# Xe_VDK_Schematic.net
KiCad netlist of a schematic drawn in Altium Designer
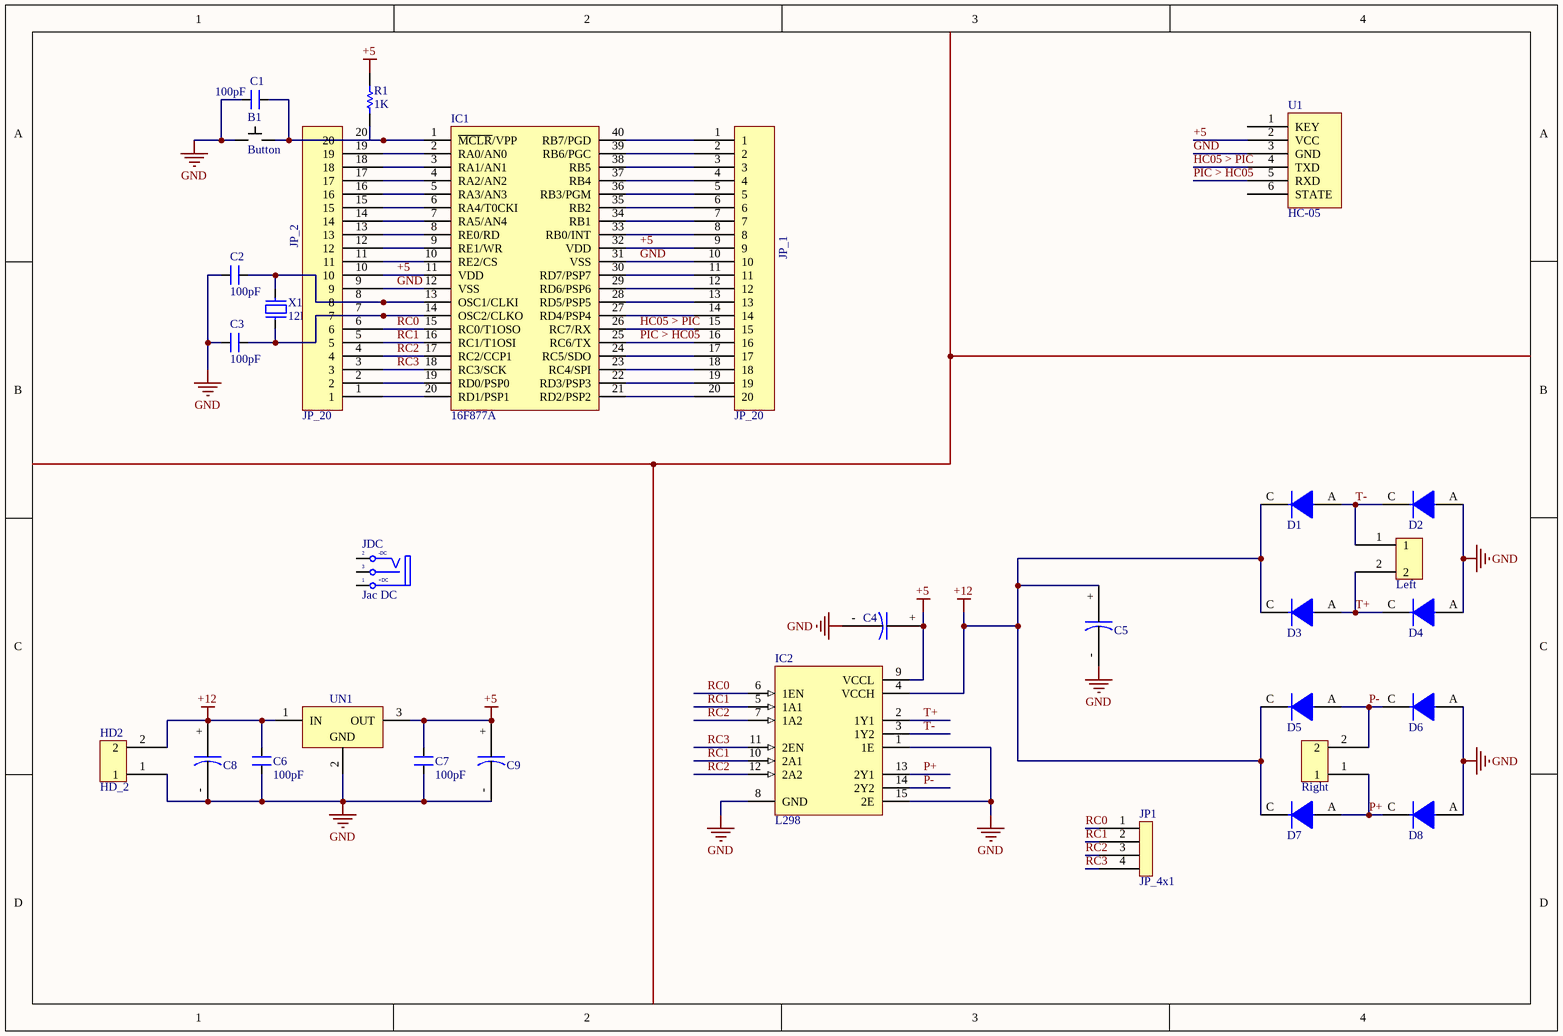
[diagram p0: Xe_VDK_Schematic.SchDoc]

(export (version "E")
  (design (tool "Eeschema 10.0.6"))
  (components
    (comp (ref "B1")
      (value "Button")
      (footprint "Button - 4-pin")
      (libsource (lib "LuongTanDat") (part "Button"))
    )
    (comp (ref "C1")
      (value "100pF")
      (footprint "CN1")
      (description "Cap np  1pF - 472pF")
      (libsource (lib "syhaunguyen") (part "CN1"))
    )
    (comp (ref "C2")
      (value "100pF")
      (footprint "CN1")
      (description "Cap np  1pF - 472pF")
      (libsource (lib "syhaunguyen") (part "CN1"))
    )
    (comp (ref "C3")
      (value "100pF")
      (footprint "CN1")
      (description "Cap np  1pF - 472pF")
      (libsource (lib "syhaunguyen") (part "CN1"))
    )
    (comp (ref "C4")
      (value "Pol-Cap")
      (footprint "Pol_200mil")
      (description "Tụ điện phân cực")
      (libsource (lib "LuongTanDat") (part "Pol-Cap"))
    )
    (comp (ref "C5")
      (value "Pol-Cap")
      (footprint "Pol_200mil")
      (description "Tụ điện phân cực")
      (libsource (lib "LuongTanDat") (part "Pol-Cap"))
    )
    (comp (ref "C6")
      (value "100pF")
      (footprint "CN1")
      (description "Cap np  1pF - 472pF")
      (libsource (lib "syhaunguyen") (part "CN1"))
    )
    (comp (ref "C7")
      (value "100pF")
      (footprint "CN1")
      (description "Cap np  1pF - 472pF")
      (libsource (lib "syhaunguyen") (part "CN1"))
    )
    (comp (ref "C8")
      (value "Pol-Cap")
      (footprint "POL_250mil")
      (description "Tụ điện phân cực")
      (libsource (lib "LuongTanDat") (part "Pol-Cap"))
    )
    (comp (ref "C9")
      (value "Pol-Cap")
      (footprint "POL_250mil")
      (description "Tụ điện phân cực")
      (libsource (lib "LuongTanDat") (part "Pol-Cap"))
    )
    (comp (ref "D1") (value "Diode") (footprint "Diode") (libsource (lib "LuongTanDat") (part "Diode")))
    (comp (ref "D2") (value "Diode") (footprint "Diode") (libsource (lib "LuongTanDat") (part "Diode")))
    (comp (ref "D3") (value "Diode") (footprint "Diode") (libsource (lib "LuongTanDat") (part "Diode")))
    (comp (ref "D4") (value "Diode") (footprint "Diode") (libsource (lib "LuongTanDat") (part "Diode")))
    (comp (ref "D5") (value "Diode") (footprint "Diode") (libsource (lib "LuongTanDat") (part "Diode")))
    (comp (ref "D6") (value "Diode") (footprint "Diode") (libsource (lib "LuongTanDat") (part "Diode")))
    (comp (ref "D7") (value "Diode") (footprint "Diode") (libsource (lib "LuongTanDat") (part "Diode")))
    (comp (ref "D8") (value "Diode") (footprint "Diode") (libsource (lib "LuongTanDat") (part "Diode")))
    (comp (ref "HD2") (value "HD_2") (footprint "Header 2") (libsource (lib "LuongTanDat") (part "HD_2")))
    (comp (ref "IC1")
      (value "16F877A")
      (footprint "DIP40/W0.6")
      (description "8K FLASH, 368B RAM, 256B EFROM")
      (fields (field (name "COPYRIGHT BY") "VanDungEvn"))
      (libsource (lib "syhaunguyen") (part "16F877"))
    )
    (comp (ref "IC2")
      (value "L298")
      (footprint "DIP15SL2")
      (description "Dual Full-H Driver")
      (fields (field (name "PUBLISHER") "Altium Limited"))
      (libsource (lib "VioletofSun") (part "L298"))
    )
    (comp (ref "JDC")
      (value "Jac DC")
      (footprint "DC0")
      (description "Jac DC input")
      (libsource (lib "ImetAltiumLibrary") (part "DCIN"))
    )
    (comp (ref "JP1") (value "JP_4x1") (footprint "JP_4x1") (libsource (lib "LuongTanDat") (part "JP_4x1")))
    (comp (ref "JP_1") (value "JP_20") (footprint "JP_20") (libsource (lib "LuongTanDat") (part "JP_20")))
    (comp (ref "JP_2") (value "JP_20") (footprint "JP_20") (libsource (lib "") (part "JP_20_1")))
    (comp (ref "Left") (value "HD_2") (footprint "Header 2") (libsource (lib "") (part "HD_2_1")))
    (comp (ref "R1")
      (value "1K")
      (footprint "RES 1/2W")
      (description "Resistor")
      (fields (field (name "Comment") "RESISTOR"))
      (libsource (lib "PIF_Library") (part "RESISTOR"))
    )
    (comp (ref "Right") (value "HD_2") (footprint "Header 2") (libsource (lib "LuongTanDat") (part "HD_2")))
    (comp (ref "U1") (value "HC-05") (footprint "HC-05") (libsource (lib "LuongTanDat") (part "HC-05")))
    (comp (ref "UN1")
      (value "LM7805")
      (footprint "QTO-220")
      (description "Positive Voltage Regulator")
      (libsource (lib "PIF_Library") (part "LM7805"))
    )
    (comp (ref "X1")
      (value "12Mhz")
      (footprint "XT2")
      (description "Crystal, 32.768 KHz, -40 to 85 degC, 3.2 x 1.5 x 0.9 mm SMD")
      (libsource (lib "ImetAltiumLibrary") (part "XT2"))
    )
  )
  (nets
    (net (code "1") (name "+5") (class "Default")
      (node (ref "C4") (pin "+") (pintype "passive"))
      (node (ref "C7") (pin "2") (pinfunction "2_2") (pintype "passive"))
      (node (ref "C9") (pin "+") (pintype "passive"))
      (node (ref "IC1") (pin "11") (pinfunction "VDD_11") (pintype "passive"))
      (node (ref "IC1") (pin "32") (pinfunction "VDD_32") (pintype "passive"))
      (node (ref "IC2") (pin "9") (pinfunction "VCCL_9") (pintype "power_in"))
      (node (ref "JP_1") (pin "9") (pinfunction "9_9") (pintype "passive"))
      (node (ref "JP_2") (pin "10") (pinfunction "10_10") (pintype "passive"))
      (node (ref "R1") (pin "2") (pinfunction "2_2") (pintype "passive"))
      (node (ref "U1") (pin "2") (pinfunction "VCC_2") (pintype "passive"))
      (node (ref "UN1") (pin "3") (pinfunction "OUT_3") (pintype "power_in"))
    )
    (net (code "2") (name "+12") (class "Default")
      (node (ref "C5") (pin "+") (pintype "passive"))
      (node (ref "C6") (pin "2") (pinfunction "2_2") (pintype "passive"))
      (node (ref "C8") (pin "+") (pintype "passive"))
      (node (ref "D1") (pin "C") (pinfunction "2_C") (pintype "passive"))
      (node (ref "D3") (pin "C") (pinfunction "2_C") (pintype "passive"))
      (node (ref "D5") (pin "C") (pinfunction "2_C") (pintype "passive"))
      (node (ref "D7") (pin "C") (pinfunction "2_C") (pintype "passive"))
      (node (ref "HD2") (pin "2") (pinfunction "2_2") (pintype "passive"))
      (node (ref "IC2") (pin "4") (pinfunction "VCCH_4") (pintype "power_in"))
      (node (ref "UN1") (pin "1") (pinfunction "IN_1") (pintype "power_in"))
    )
    (net (code "3") (name "/HC05 > PIC") (class "Default")
      (node (ref "IC1") (pin "26") (pinfunction "RC7/RX_26") (pintype "passive"))
      (node (ref "JP_1") (pin "15") (pinfunction "15_15") (pintype "passive"))
      (node (ref "U1") (pin "4") (pinfunction "TXD_4") (pintype "passive"))
    )
    (net (code "4") (name "/P+") (class "Default")
      (node (ref "D7") (pin "A") (pinfunction "1_A") (pintype "passive"))
      (node (ref "D8") (pin "C") (pinfunction "2_C") (pintype "passive"))
      (node (ref "IC2") (pin "13") (pinfunction "2Y1_13") (pintype "tri_state"))
      (node (ref "Right") (pin "1") (pinfunction "1_1") (pintype "passive"))
    )
    (net (code "5") (name "/P-") (class "Default")
      (node (ref "D5") (pin "A") (pinfunction "1_A") (pintype "passive"))
      (node (ref "D6") (pin "C") (pinfunction "2_C") (pintype "passive"))
      (node (ref "IC2") (pin "14") (pinfunction "2Y2_14") (pintype "tri_state"))
      (node (ref "Right") (pin "2") (pinfunction "2_2") (pintype "passive"))
    )
    (net (code "6") (name "/PIC > HC05") (class "Default")
      (node (ref "IC1") (pin "25") (pinfunction "RC6/TX_25") (pintype "passive"))
      (node (ref "JP_1") (pin "16") (pinfunction "16_16") (pintype "passive"))
      (node (ref "U1") (pin "5") (pinfunction "RXD_5") (pintype "passive"))
    )
    (net (code "7") (name "/RC0") (class "Default")
      (node (ref "IC1") (pin "15") (pinfunction "RC0/T1OSO_15") (pintype "passive"))
      (node (ref "IC2") (pin "6") (pinfunction "1EN_6") (pintype "input"))
      (node (ref "JP1") (pin "1") (pinfunction "1_1") (pintype "passive"))
      (node (ref "JP_2") (pin "6") (pinfunction "6_6") (pintype "passive"))
    )
    (net (code "8") (name "/RC1") (class "Default")
      (node (ref "IC1") (pin "16") (pinfunction "RC1/T1OSI_16") (pintype "passive"))
      (node (ref "IC2") (pin "10") (pinfunction "2A1_10") (pintype "input"))
      (node (ref "IC2") (pin "5") (pinfunction "1A1_5") (pintype "input"))
      (node (ref "JP1") (pin "2") (pinfunction "2_2") (pintype "passive"))
      (node (ref "JP_2") (pin "5") (pinfunction "5_5") (pintype "passive"))
    )
    (net (code "9") (name "/RC2") (class "Default")
      (node (ref "IC1") (pin "17") (pinfunction "RC2/CCP1_17") (pintype "passive"))
      (node (ref "IC2") (pin "12") (pinfunction "2A2_12") (pintype "input"))
      (node (ref "IC2") (pin "7") (pinfunction "1A2_7") (pintype "input"))
      (node (ref "JP1") (pin "3") (pinfunction "3_3") (pintype "passive"))
      (node (ref "JP_2") (pin "4") (pinfunction "4_4") (pintype "passive"))
    )
    (net (code "10") (name "/RC3") (class "Default")
      (node (ref "IC1") (pin "18") (pinfunction "RC3/SCK_18") (pintype "passive"))
      (node (ref "IC2") (pin "11") (pinfunction "2EN_11") (pintype "input"))
      (node (ref "JP1") (pin "4") (pinfunction "4_4") (pintype "passive"))
      (node (ref "JP_2") (pin "3") (pinfunction "3_3") (pintype "passive"))
    )
    (net (code "11") (name "/T+") (class "Default")
      (node (ref "D3") (pin "A") (pinfunction "1_A") (pintype "passive"))
      (node (ref "D4") (pin "C") (pinfunction "2_C") (pintype "passive"))
      (node (ref "IC2") (pin "2") (pinfunction "1Y1_2") (pintype "tri_state"))
      (node (ref "Left") (pin "2") (pinfunction "2_2") (pintype "passive"))
    )
    (net (code "12") (name "/T-") (class "Default")
      (node (ref "D1") (pin "A") (pinfunction "1_A") (pintype "passive"))
      (node (ref "D2") (pin "C") (pinfunction "2_C") (pintype "passive"))
      (node (ref "IC2") (pin "3") (pinfunction "1Y2_3") (pintype "tri_state"))
      (node (ref "Left") (pin "1") (pinfunction "1_1") (pintype "passive"))
    )
    (net (code "13") (name "GND") (class "Default")
      (node (ref "B1") (pin "1") (pinfunction "0_1") (pintype "passive"))
      (node (ref "C1") (pin "1") (pinfunction "1_1") (pintype "passive"))
      (node (ref "C2") (pin "1") (pinfunction "1_1") (pintype "passive"))
      (node (ref "C3") (pin "1") (pinfunction "1_1") (pintype "passive"))
      (node (ref "C4") (pin "-") (pintype "passive"))
      (node (ref "C5") (pin "-") (pintype "passive"))
      (node (ref "C6") (pin "1") (pinfunction "1_1") (pintype "passive"))
      (node (ref "C7") (pin "1") (pinfunction "1_1") (pintype "passive"))
      (node (ref "C8") (pin "-") (pintype "passive"))
      (node (ref "C9") (pin "-") (pintype "passive"))
      (node (ref "D2") (pin "A") (pinfunction "1_A") (pintype "passive"))
      (node (ref "D4") (pin "A") (pinfunction "1_A") (pintype "passive"))
      (node (ref "D6") (pin "A") (pinfunction "1_A") (pintype "passive"))
      (node (ref "D8") (pin "A") (pinfunction "1_A") (pintype "passive"))
      (node (ref "HD2") (pin "1") (pinfunction "1_1") (pintype "passive"))
      (node (ref "IC1") (pin "12") (pinfunction "VSS_12") (pintype "passive"))
      (node (ref "IC1") (pin "31") (pinfunction "VSS_31") (pintype "passive"))
      (node (ref "IC2") (pin "1") (pinfunction "1E_1") (pintype "passive"))
      (node (ref "IC2") (pin "15") (pinfunction "2E_15") (pintype "passive"))
      (node (ref "IC2") (pin "8") (pinfunction "GND_8") (pintype "power_in"))
      (node (ref "JP_1") (pin "10") (pinfunction "10_10") (pintype "passive"))
      (node (ref "JP_2") (pin "9") (pinfunction "9_9") (pintype "passive"))
      (node (ref "U1") (pin "3") (pinfunction "GND_3") (pintype "passive"))
      (node (ref "UN1") (pin "2") (pinfunction "GND_2") (pintype "power_in"))
    )
    (net (code "14") (name "Net-(B1-10)") (class "Default")
      (node (ref "B1") (pin "2") (pinfunction "10_2") (pintype "passive"))
      (node (ref "C1") (pin "2") (pinfunction "2_2") (pintype "passive"))
      (node (ref "IC1") (pin "1") (pinfunction "~{MCLR}/VPP_1") (pintype "passive"))
      (node (ref "JP_2") (pin "20") (pinfunction "20_20") (pintype "passive"))
      (node (ref "R1") (pin "1") (pinfunction "1_1") (pintype "passive"))
    )
    (net (code "15") (name "Net-(IC1-OSC1{slash}CLKI)") (class "Default")
      (node (ref "C2") (pin "2") (pinfunction "2_2") (pintype "passive"))
      (node (ref "IC1") (pin "13") (pinfunction "OSC1/CLKI_13") (pintype "passive"))
      (node (ref "JP_2") (pin "8") (pinfunction "8_8") (pintype "passive"))
      (node (ref "X1") (pin "2") (pinfunction "2_2") (pintype "passive"))
    )
    (net (code "16") (name "Net-(IC1-OSC2{slash}CLKO)") (class "Default")
      (node (ref "C3") (pin "2") (pinfunction "2_2") (pintype "passive"))
      (node (ref "IC1") (pin "14") (pinfunction "OSC2/CLKO_14") (pintype "passive"))
      (node (ref "JP_2") (pin "7") (pinfunction "7_7") (pintype "passive"))
      (node (ref "X1") (pin "1") (pinfunction "1_1") (pintype "passive"))
    )
    (net (code "17") (name "Net-(IC1-RA0{slash}AN0)") (class "Default")
      (node (ref "IC1") (pin "2") (pinfunction "RA0/AN0_2") (pintype "passive"))
      (node (ref "JP_2") (pin "19") (pinfunction "19_19") (pintype "passive"))
    )
    (net (code "18") (name "Net-(IC1-RA1{slash}AN1)") (class "Default")
      (node (ref "IC1") (pin "3") (pinfunction "RA1/AN1_3") (pintype "passive"))
      (node (ref "JP_2") (pin "18") (pinfunction "18_18") (pintype "passive"))
    )
    (net (code "19") (name "Net-(IC1-RA2{slash}AN2)") (class "Default")
      (node (ref "IC1") (pin "4") (pinfunction "RA2/AN2_4") (pintype "passive"))
      (node (ref "JP_2") (pin "17") (pinfunction "17_17") (pintype "passive"))
    )
    (net (code "20") (name "Net-(IC1-RA3{slash}AN3)") (class "Default")
      (node (ref "IC1") (pin "5") (pinfunction "RA3/AN3_5") (pintype "passive"))
      (node (ref "JP_2") (pin "16") (pinfunction "16_16") (pintype "passive"))
    )
    (net (code "21") (name "Net-(IC1-RA4{slash}T0CKI)") (class "Default")
      (node (ref "IC1") (pin "6") (pinfunction "RA4/T0CKI_6") (pintype "passive"))
      (node (ref "JP_2") (pin "15") (pinfunction "15_15") (pintype "passive"))
    )
    (net (code "22") (name "Net-(IC1-RA5{slash}AN4)") (class "Default")
      (node (ref "IC1") (pin "7") (pinfunction "RA5/AN4_7") (pintype "passive"))
      (node (ref "JP_2") (pin "14") (pinfunction "14_14") (pintype "passive"))
    )
    (net (code "23") (name "Net-(IC1-RB0{slash}INT)") (class "Default")
      (node (ref "IC1") (pin "33") (pinfunction "RB0/INT_33") (pintype "passive"))
      (node (ref "JP_1") (pin "8") (pinfunction "8_8") (pintype "passive"))
    )
    (net (code "24") (name "Net-(IC1-RB1)") (class "Default")
      (node (ref "IC1") (pin "34") (pinfunction "RB1_34") (pintype "passive"))
      (node (ref "JP_1") (pin "7") (pinfunction "7_7") (pintype "passive"))
    )
    (net (code "25") (name "Net-(IC1-RB2)") (class "Default")
      (node (ref "IC1") (pin "35") (pinfunction "RB2_35") (pintype "passive"))
      (node (ref "JP_1") (pin "6") (pinfunction "6_6") (pintype "passive"))
    )
    (net (code "26") (name "Net-(IC1-RB3{slash}PGM)") (class "Default")
      (node (ref "IC1") (pin "36") (pinfunction "RB3/PGM_36") (pintype "passive"))
      (node (ref "JP_1") (pin "5") (pinfunction "5_5") (pintype "passive"))
    )
    (net (code "27") (name "Net-(IC1-RB4)") (class "Default")
      (node (ref "IC1") (pin "37") (pinfunction "RB4_37") (pintype "passive"))
      (node (ref "JP_1") (pin "4") (pinfunction "4_4") (pintype "passive"))
    )
    (net (code "28") (name "Net-(IC1-RB5)") (class "Default")
      (node (ref "IC1") (pin "38") (pinfunction "RB5_38") (pintype "passive"))
      (node (ref "JP_1") (pin "3") (pinfunction "3_3") (pintype "passive"))
    )
    (net (code "29") (name "Net-(IC1-RB6{slash}PGC)") (class "Default")
      (node (ref "IC1") (pin "39") (pinfunction "RB6/PGC_39") (pintype "passive"))
      (node (ref "JP_1") (pin "2") (pinfunction "2_2") (pintype "passive"))
    )
    (net (code "30") (name "Net-(IC1-RB7{slash}PGD)") (class "Default")
      (node (ref "IC1") (pin "40") (pinfunction "RB7/PGD_40") (pintype "passive"))
      (node (ref "JP_1") (pin "1") (pinfunction "1_1") (pintype "passive"))
    )
    (net (code "31") (name "Net-(IC1-RC4{slash}SPI)") (class "Default")
      (node (ref "IC1") (pin "23") (pinfunction "RC4/SPI_23") (pintype "passive"))
      (node (ref "JP_1") (pin "18") (pinfunction "18_18") (pintype "passive"))
    )
    (net (code "32") (name "Net-(IC1-RC5{slash}SDO)") (class "Default")
      (node (ref "IC1") (pin "24") (pinfunction "RC5/SDO_24") (pintype "passive"))
      (node (ref "JP_1") (pin "17") (pinfunction "17_17") (pintype "passive"))
    )
    (net (code "33") (name "Net-(IC1-RD0{slash}PSP0)") (class "Default")
      (node (ref "IC1") (pin "19") (pinfunction "RD0/PSP0_19") (pintype "passive"))
      (node (ref "JP_2") (pin "2") (pinfunction "2_2") (pintype "passive"))
    )
    (net (code "34") (name "Net-(IC1-RD1{slash}PSP1)") (class "Default")
      (node (ref "IC1") (pin "20") (pinfunction "RD1/PSP1_20") (pintype "passive"))
      (node (ref "JP_2") (pin "1") (pinfunction "1_1") (pintype "passive"))
    )
    (net (code "35") (name "Net-(IC1-RD2{slash}PSP2)") (class "Default")
      (node (ref "IC1") (pin "21") (pinfunction "RD2/PSP2_21") (pintype "passive"))
      (node (ref "JP_1") (pin "20") (pinfunction "20_20") (pintype "passive"))
    )
    (net (code "36") (name "Net-(IC1-RD3{slash}PSP3)") (class "Default")
      (node (ref "IC1") (pin "22") (pinfunction "RD3/PSP3_22") (pintype "passive"))
      (node (ref "JP_1") (pin "19") (pinfunction "19_19") (pintype "passive"))
    )
    (net (code "37") (name "Net-(IC1-RD4{slash}PSP4)") (class "Default")
      (node (ref "IC1") (pin "27") (pinfunction "RD4/PSP4_27") (pintype "passive"))
      (node (ref "JP_1") (pin "14") (pinfunction "14_14") (pintype "passive"))
    )
    (net (code "38") (name "Net-(IC1-RD5{slash}PSP5)") (class "Default")
      (node (ref "IC1") (pin "28") (pinfunction "RD5/PSP5_28") (pintype "passive"))
      (node (ref "JP_1") (pin "13") (pinfunction "13_13") (pintype "passive"))
    )
    (net (code "39") (name "Net-(IC1-RD6{slash}PSP6)") (class "Default")
      (node (ref "IC1") (pin "29") (pinfunction "RD6/PSP6_29") (pintype "passive"))
      (node (ref "JP_1") (pin "12") (pinfunction "12_12") (pintype "passive"))
    )
    (net (code "40") (name "Net-(IC1-RD7{slash}PSP7)") (class "Default")
      (node (ref "IC1") (pin "30") (pinfunction "RD7/PSP7_30") (pintype "passive"))
      (node (ref "JP_1") (pin "11") (pinfunction "11_11") (pintype "passive"))
    )
    (net (code "41") (name "Net-(IC1-RE0{slash}RD)") (class "Default")
      (node (ref "IC1") (pin "8") (pinfunction "RE0/RD_8") (pintype "passive"))
      (node (ref "JP_2") (pin "13") (pinfunction "13_13") (pintype "passive"))
    )
    (net (code "42") (name "Net-(IC1-RE1{slash}WR)") (class "Default")
      (node (ref "IC1") (pin "9") (pinfunction "RE1/WR_9") (pintype "passive"))
      (node (ref "JP_2") (pin "12") (pinfunction "12_12") (pintype "passive"))
    )
    (net (code "43") (name "Net-(IC1-RE2{slash}CS)") (class "Default")
      (node (ref "IC1") (pin "10") (pinfunction "RE2/CS_10") (pintype "passive"))
      (node (ref "JP_2") (pin "11") (pinfunction "11_11") (pintype "passive"))
    )
    (net (code "44") (name "unconnected-(JDC-S-Pad3)") (class "Default")
      (node (ref "JDC") (pin "3") (pinfunction "S_3") (pintype "power_in"))
    )
    (net (code "45") (name "unconnected-(JDC-T-Pad1)") (class "Default")
      (node (ref "JDC") (pin "1") (pinfunction "T_1") (pintype "passive"))
    )
    (net (code "46") (name "unconnected-(JDC-TN-Pad2)") (class "Default")
      (node (ref "JDC") (pin "2") (pinfunction "TN_2") (pintype "passive"))
    )
    (net (code "47") (name "unconnected-(U1-KEY-Pad1)") (class "Default")
      (node (ref "U1") (pin "1") (pinfunction "KEY_1") (pintype "passive"))
    )
    (net (code "48") (name "unconnected-(U1-STATE-Pad6)") (class "Default")
      (node (ref "U1") (pin "6") (pinfunction "STATE_6") (pintype "passive"))
    )
  )
)
